# 20190501.net
KiCad netlist of a schematic drawn in EAGLE
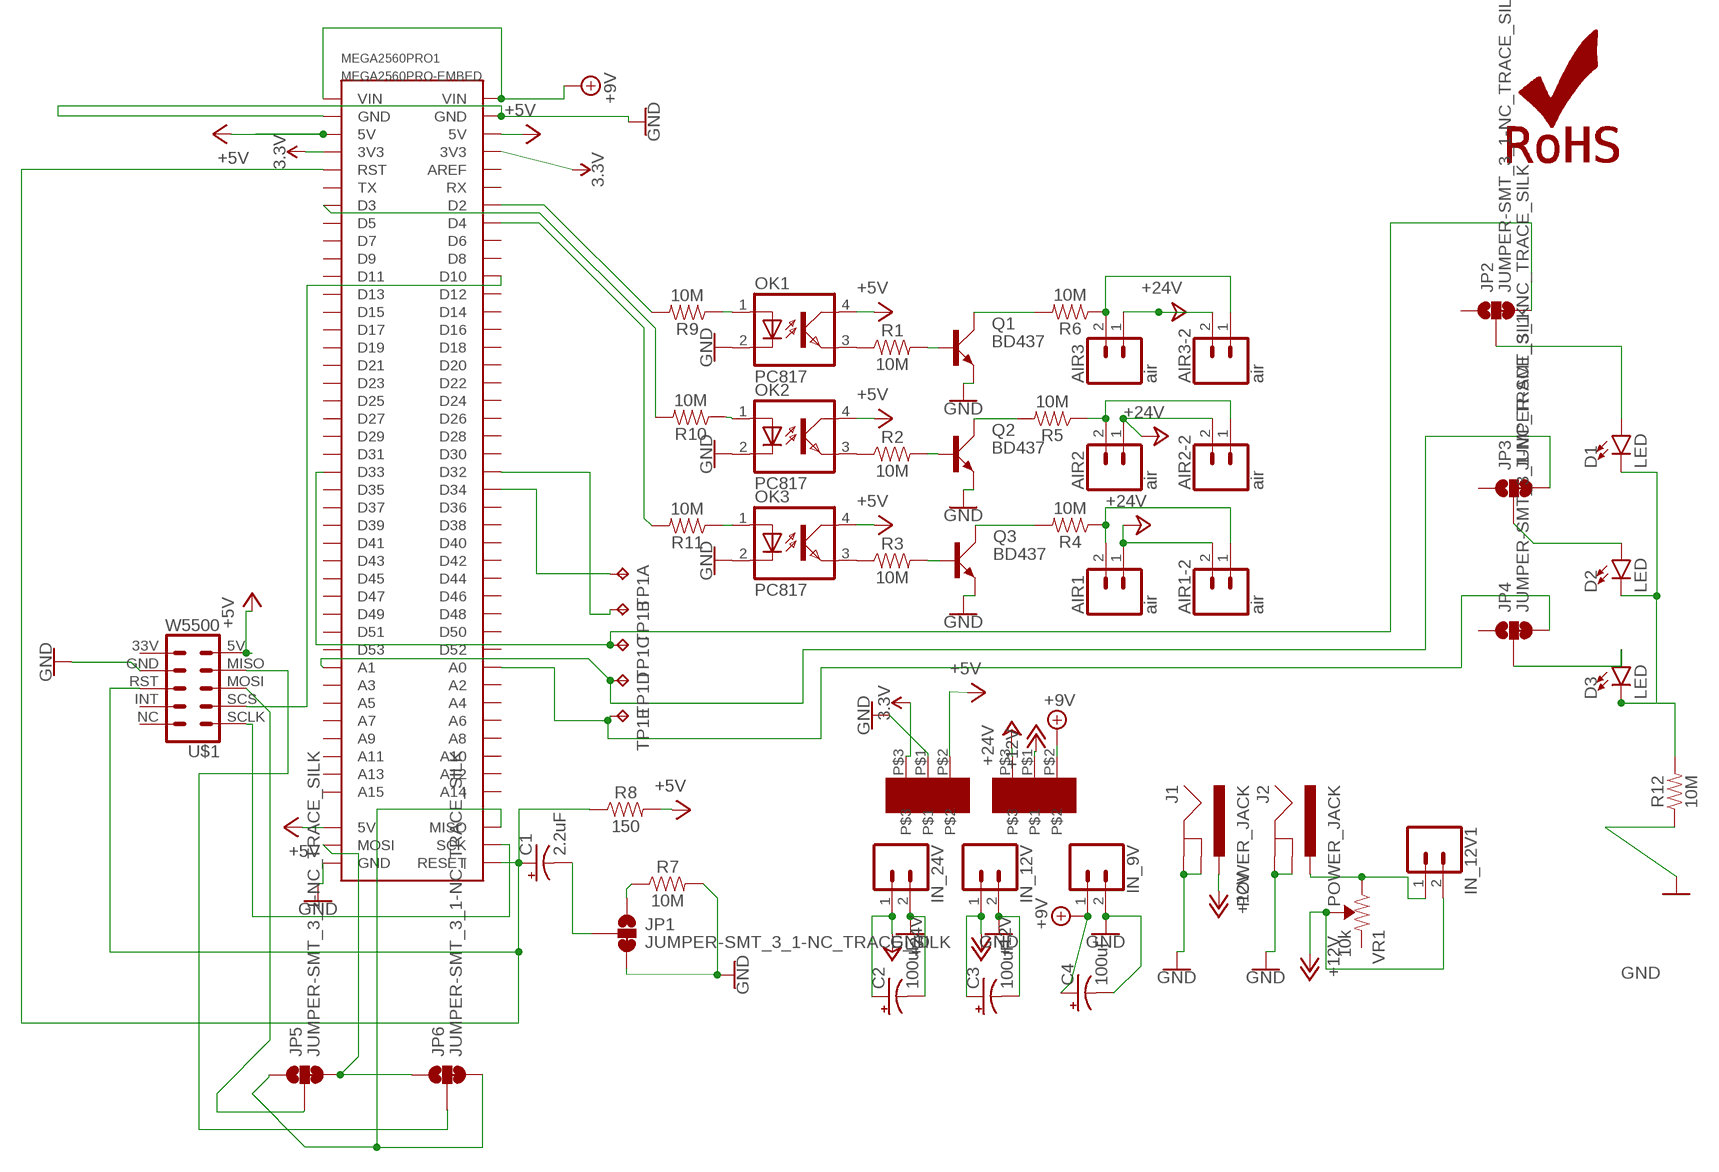
[diagram p0: schematic, sheet 1]

(export (version "E")
  (design (tool "Eeschema 10.0.6"))
  (components
    (comp (ref "AIR1")
      (value "air")
      (footprint "eagle-import:MOLEX-1X2_LOCK")
      (libsource (lib "eagle-import") (part "CONN_02POLAR_LOCK"))
    )
    (comp (ref "AIR1-2")
      (value "air")
      (footprint "eagle-import:1X02")
      (libsource (lib "eagle-import") (part "CONN_02"))
    )
    (comp (ref "AIR2")
      (value "air")
      (footprint "eagle-import:MOLEX-1X2_LOCK")
      (libsource (lib "eagle-import") (part "CONN_02POLAR_LOCK"))
    )
    (comp (ref "AIR2-2")
      (value "air")
      (footprint "eagle-import:1X02")
      (libsource (lib "eagle-import") (part "CONN_02"))
    )
    (comp (ref "AIR3")
      (value "air")
      (footprint "eagle-import:MOLEX-1X2_LOCK")
      (libsource (lib "eagle-import") (part "CONN_02POLAR_LOCK"))
    )
    (comp (ref "AIR3-2")
      (value "air")
      (footprint "eagle-import:1X02")
      (libsource (lib "eagle-import") (part "CONN_02"))
    )
    (comp (ref "C1")
      (value "2.2uF")
      (footprint "eagle-import:CPOL-RADIAL-2.5MM-5MM-KIT")
      (libsource (lib "eagle-import") (part "10UF-POLAR-RADIAL-2.5MM-KIT-25V-20%"))
    )
    (comp (ref "C2")
      (value "100uF")
      (footprint "eagle-import:CPOL-RADIAL-2.5MM-6.5MM")
      (libsource (lib "eagle-import") (part "100UF-POLAR-RADIAL-2.5MM-25V-20%"))
    )
    (comp (ref "C3")
      (value "100uF")
      (footprint "eagle-import:CPOL-RADIAL-2.5MM-6.5MM")
      (libsource (lib "eagle-import") (part "100UF-POLAR-RADIAL-2.5MM-25V-20%"))
    )
    (comp (ref "C4")
      (value "100uF")
      (footprint "eagle-import:CPOL-RADIAL-2.5MM-6.5MM")
      (libsource (lib "eagle-import") (part "100UF-POLAR-RADIAL-2.5MM-25V-20%"))
    )
    (comp (ref "D1")
      (value "LED")
      (footprint "eagle-import:LED_5MM")
      (libsource (lib "eagle-import") (part "LED5MM"))
    )
    (comp (ref "D2")
      (value "LED")
      (footprint "eagle-import:LED_5MM")
      (libsource (lib "eagle-import") (part "LED5MM"))
    )
    (comp (ref "D3")
      (value "LED")
      (footprint "eagle-import:LED_5MM")
      (libsource (lib "eagle-import") (part "LED5MM"))
    )
    (comp (ref "IN_9V")
      (value "CONN_02POLAR_LOCK")
      (footprint "eagle-import:MOLEX-1X2_LOCK")
      (libsource (lib "eagle-import") (part "CONN_02POLAR_LOCK"))
    )
    (comp (ref "IN_12V")
      (value "CONN_02POLAR_LOCK")
      (footprint "eagle-import:MOLEX-1X2_LOCK")
      (libsource (lib "eagle-import") (part "CONN_02POLAR_LOCK"))
    )
    (comp (ref "IN_12V1")
      (value "CONN_02POLAR_LOCK")
      (footprint "eagle-import:MOLEX-1X2_LOCK")
      (libsource (lib "eagle-import") (part "CONN_02POLAR_LOCK"))
    )
    (comp (ref "IN_24V")
      (value "CONN_02POLAR_LOCK")
      (footprint "eagle-import:MOLEX-1X2_LOCK")
      (libsource (lib "eagle-import") (part "CONN_02POLAR_LOCK"))
    )
    (comp (ref "J1")
      (value "POWER_JACK")
      (footprint "eagle-import:POWER_JACK_PTH")
      (libsource (lib "eagle-import") (part "POWER_JACK"))
    )
    (comp (ref "J2")
      (value "POWER_JACK")
      (footprint "eagle-import:POWER_JACK_PTH")
      (libsource (lib "eagle-import") (part "POWER_JACK"))
    )
    (comp (ref "JP1")
      (value "JUMPER-SMT_3_1-NC_TRACE_SILK")
      (footprint "eagle-import:SMT-JUMPER_3_1-NC_TRACE_SILK")
      (libsource (lib "eagle-import") (part "JUMPER-SMT_3_1-NC_TRACE_SILK"))
    )
    (comp (ref "JP2")
      (value "JUMPER-SMT_3_1-NC_TRACE_SILK")
      (footprint "eagle-import:SMT-JUMPER_3_1-NC_TRACE_SILK")
      (libsource (lib "eagle-import") (part "JUMPER-SMT_3_1-NC_TRACE_SILK"))
    )
    (comp (ref "JP3")
      (value "JUMPER-SMT_3_1-NC_TRACE_SILK")
      (footprint "eagle-import:SMT-JUMPER_3_1-NC_TRACE_SILK")
      (libsource (lib "eagle-import") (part "JUMPER-SMT_3_1-NC_TRACE_SILK"))
    )
    (comp (ref "JP4")
      (value "JUMPER-SMT_3_1-NC_TRACE_SILK")
      (footprint "eagle-import:SMT-JUMPER_3_1-NC_TRACE_SILK")
      (libsource (lib "eagle-import") (part "JUMPER-SMT_3_1-NC_TRACE_SILK"))
    )
    (comp (ref "JP5")
      (value "JUMPER-SMT_3_1-NC_TRACE_SILK")
      (footprint "eagle-import:SMT-JUMPER_3_1-NC_TRACE_SILK")
      (libsource (lib "eagle-import") (part "JUMPER-SMT_3_1-NC_TRACE_SILK"))
    )
    (comp (ref "JP6")
      (value "JUMPER-SMT_3_1-NC_TRACE_SILK")
      (footprint "eagle-import:SMT-JUMPER_3_1-NC_TRACE_SILK")
      (libsource (lib "eagle-import") (part "JUMPER-SMT_3_1-NC_TRACE_SILK"))
    )
    (comp (ref "LOGO1")
      (value "ROHS_LOGO")
      (footprint "eagle-import:ROHS_LOGO_0.18_IN")
      (libsource (lib "eagle-import") (part "ROHS_LOGO"))
    )
    (comp (ref "MEGA2560PRO1")
      (value "MEGA2560PRO-EMBED")
      (footprint "eagle-import:MEGA2560PRO-EMBED")
      (libsource (lib "eagle-import") (part "MEGA2560PRO-EMBED"))
    )
    (comp (ref "OK1")
      (value "PC817")
      (footprint "eagle-import:DIL04")
      (fields (field (name "MPN") "PC817X4J000F"))
      (libsource (lib "eagle-import") (part "PC817"))
    )
    (comp (ref "OK2")
      (value "PC817")
      (footprint "eagle-import:DIL04")
      (fields (field (name "MPN") "PC817X4J000F"))
      (libsource (lib "eagle-import") (part "PC817"))
    )
    (comp (ref "OK3")
      (value "PC817")
      (footprint "eagle-import:DIL04")
      (fields (field (name "MPN") "PC817X4J000F"))
      (libsource (lib "eagle-import") (part "PC817"))
    )
    (comp (ref "Q1")
      (value "BD437")
      (footprint "eagle-import:TO126AV")
      (libsource (lib "eagle-import") (part "BD437"))
    )
    (comp (ref "Q2")
      (value "BD437")
      (footprint "eagle-import:TO126AV")
      (libsource (lib "eagle-import") (part "BD437"))
    )
    (comp (ref "Q3")
      (value "BD437")
      (footprint "eagle-import:TO126AV")
      (libsource (lib "eagle-import") (part "BD437"))
    )
    (comp (ref "R1")
      (value "10M")
      (footprint "eagle-import:AXIAL-0.3")
      (libsource (lib "eagle-import") (part "10MOHM-HORIZ-1/4W-5%"))
    )
    (comp (ref "R2")
      (value "10M")
      (footprint "eagle-import:AXIAL-0.3")
      (libsource (lib "eagle-import") (part "10MOHM-HORIZ-1/4W-5%"))
    )
    (comp (ref "R3")
      (value "10M")
      (footprint "eagle-import:AXIAL-0.3")
      (libsource (lib "eagle-import") (part "10MOHM-HORIZ-1/4W-5%"))
    )
    (comp (ref "R4")
      (value "10M")
      (footprint "eagle-import:AXIAL-0.3")
      (libsource (lib "eagle-import") (part "10MOHM-HORIZ-1/4W-5%"))
    )
    (comp (ref "R5")
      (value "10M")
      (footprint "eagle-import:AXIAL-0.3")
      (libsource (lib "eagle-import") (part "10MOHM-HORIZ-1/4W-5%"))
    )
    (comp (ref "R6")
      (value "10M")
      (footprint "eagle-import:AXIAL-0.3")
      (libsource (lib "eagle-import") (part "10MOHM-HORIZ-1/4W-5%"))
    )
    (comp (ref "R7")
      (value "10M")
      (footprint "eagle-import:AXIAL-0.3")
      (libsource (lib "eagle-import") (part "10MOHM-HORIZ-1/4W-5%"))
    )
    (comp (ref "R8")
      (value "150")
      (footprint "eagle-import:AXIAL-0.3")
      (libsource (lib "eagle-import") (part "10MOHM-HORIZ-1/4W-5%"))
    )
    (comp (ref "R9")
      (value "10M")
      (footprint "eagle-import:AXIAL-0.3")
      (libsource (lib "eagle-import") (part "10MOHM-HORIZ-1/4W-5%"))
    )
    (comp (ref "R10")
      (value "10M")
      (footprint "eagle-import:AXIAL-0.3")
      (libsource (lib "eagle-import") (part "10MOHM-HORIZ-1/4W-5%"))
    )
    (comp (ref "R11")
      (value "10M")
      (footprint "eagle-import:AXIAL-0.3")
      (libsource (lib "eagle-import") (part "10MOHM-HORIZ-1/4W-5%"))
    )
    (comp (ref "R12")
      (value "10M")
      (footprint "eagle-import:AXIAL-0.3")
      (libsource (lib "eagle-import") (part "10MOHM-HORIZ-1/4W-5%"))
    )
    (comp (ref "TP1")
      (value "TP5P5-25-13")
      (footprint "eagle-import:P5-25-13")
      (libsource (lib "eagle-import") (part "TP5P5-25-13"))
    )
    (comp (ref "U$1")
      (value "W5500")
      (footprint "eagle-import:W5500")
      (libsource (lib "eagle-import") (part "W5500"))
    )
    (comp (ref "U$2")
      (value "AC_3PINAC3PIN7MM")
      (footprint "eagle-import:AC3PIN7MM")
      (libsource (lib "eagle-import") (part "AC_3PINAC3PIN7MM"))
    )
    (comp (ref "U$4")
      (value "AC_3PINAC3PIN7MM")
      (footprint "eagle-import:AC3PIN7MM")
      (libsource (lib "eagle-import") (part "AC_3PINAC3PIN7MM"))
    )
    (comp (ref "VR1")
      (value "10k")
      (footprint "eagle-import:TRIMPOT-PTH-3386U")
      (libsource (lib "eagle-import") (part "TRIMPOT-PTH-10MM-KNOB-1/2W-10%"))
    )
  )
  (nets
    (net (code "1") (name "+5V") (class "Default")
      (node (ref "MEGA2560PRO1") (pin "5V@1") (pinfunction "5V_5V@1") (pintype "bidirectional"))
      (node (ref "MEGA2560PRO1") (pin "5V@2") (pinfunction "5V_5V@2") (pintype "bidirectional"))
      (node (ref "MEGA2560PRO1") (pin "5V@3") (pinfunction "5V_5V@3") (pintype "bidirectional"))
      (node (ref "OK1") (pin "4") (pinfunction "COL_4") (pintype "passive"))
      (node (ref "OK2") (pin "4") (pinfunction "COL_4") (pintype "passive"))
      (node (ref "OK3") (pin "4") (pinfunction "COL_4") (pintype "passive"))
      (node (ref "R8") (pin "P$2") (pinfunction "2_P$2") (pintype "passive"))
      (node (ref "U$1") (pin "5V") (pinfunction "9_5V") (pintype "passive"))
      (node (ref "U$4") (pin "P$2") (pinfunction "P$2_P$2") (pintype "bidirectional"))
    )
    (net (code "2") (name "+9V") (class "Default")
      (node (ref "C4") (pin "1") (pinfunction "+_1") (pintype "passive"))
      (node (ref "IN_9V") (pin "1") (pinfunction "1_1") (pintype "passive"))
      (node (ref "MEGA2560PRO1") (pin "VIN@1") (pinfunction "VIN_VIN@1") (pintype "bidirectional"))
      (node (ref "MEGA2560PRO1") (pin "VIN@2") (pinfunction "VIN_VIN@2") (pintype "bidirectional"))
      (node (ref "U$2") (pin "P$2") (pinfunction "P$2_P$2") (pintype "bidirectional"))
    )
    (net (code "3") (name "+12V") (class "Default")
      (node (ref "C3") (pin "1") (pinfunction "+_1") (pintype "passive"))
      (node (ref "IN_12V") (pin "1") (pinfunction "1_1") (pintype "passive"))
      (node (ref "IN_12V1") (pin "2") (pinfunction "2_2") (pintype "passive"))
      (node (ref "J1") (pin "PWR") (pinfunction "PWR_PWR") (pintype "bidirectional"))
      (node (ref "U$2") (pin "P$1") (pinfunction "P$1_P$1") (pintype "bidirectional"))
      (node (ref "VR1") (pin "2") (pinfunction "WIPER_2") (pintype "passive"))
    )
    (net (code "4") (name "+24V") (class "Default")
      (node (ref "AIR1") (pin "1") (pinfunction "1_1") (pintype "passive"))
      (node (ref "AIR1-2") (pin "2") (pinfunction "2_2") (pintype "passive"))
      (node (ref "AIR2") (pin "1") (pinfunction "1_1") (pintype "passive"))
      (node (ref "AIR2-2") (pin "2") (pinfunction "2_2") (pintype "passive"))
      (node (ref "AIR3") (pin "1") (pinfunction "1_1") (pintype "passive"))
      (node (ref "AIR3-2") (pin "2") (pinfunction "2_2") (pintype "passive"))
      (node (ref "C2") (pin "1") (pinfunction "+_1") (pintype "passive"))
      (node (ref "IN_24V") (pin "1") (pinfunction "1_1") (pintype "passive"))
      (node (ref "U$2") (pin "P$3") (pinfunction "P$3_P$3") (pintype "bidirectional"))
    )
    (net (code "5") (name "3.3V") (class "Default")
      (node (ref "MEGA2560PRO1") (pin "3V3@1") (pinfunction "3V3_3V3@1") (pintype "bidirectional"))
      (node (ref "MEGA2560PRO1") (pin "3V3@2") (pinfunction "3V3_3V3@2") (pintype "bidirectional"))
      (node (ref "U$4") (pin "P$3") (pinfunction "P$3_P$3") (pintype "bidirectional"))
    )
    (net (code "6") (name "GND") (class "Default")
      (node (ref "C2") (pin "2") (pinfunction "-_2") (pintype "passive"))
      (node (ref "C3") (pin "2") (pinfunction "-_2") (pintype "passive"))
      (node (ref "C4") (pin "2") (pinfunction "-_2") (pintype "passive"))
      (node (ref "IN_12V") (pin "2") (pinfunction "2_2") (pintype "passive"))
      (node (ref "IN_24V") (pin "2") (pinfunction "2_2") (pintype "passive"))
      (node (ref "IN_9V") (pin "2") (pinfunction "2_2") (pintype "passive"))
      (node (ref "J1") (pin "GND") (pinfunction "GND_GND") (pintype "bidirectional"))
      (node (ref "J1") (pin "GNDBREAK") (pinfunction "GNDBREAK_GNDBREAK") (pintype "bidirectional"))
      (node (ref "J2") (pin "GND") (pinfunction "GND_GND") (pintype "bidirectional"))
      (node (ref "J2") (pin "GNDBREAK") (pinfunction "GNDBREAK_GNDBREAK") (pintype "bidirectional"))
      (node (ref "JP1") (pin "3") (pinfunction "3_3") (pintype "passive"))
      (node (ref "MEGA2560PRO1") (pin "GND@1") (pinfunction "GND_GND@1") (pintype "bidirectional"))
      (node (ref "MEGA2560PRO1") (pin "GND@2") (pinfunction "GND_GND@2") (pintype "bidirectional"))
      (node (ref "MEGA2560PRO1") (pin "GND@3") (pinfunction "GND_GND@3") (pintype "bidirectional"))
      (node (ref "OK1") (pin "2") (pinfunction "C_2") (pintype "passive"))
      (node (ref "OK2") (pin "2") (pinfunction "C_2") (pintype "passive"))
      (node (ref "OK3") (pin "2") (pinfunction "C_2") (pintype "passive"))
      (node (ref "Q1") (pin "E") (pinfunction "E_E") (pintype "passive"))
      (node (ref "Q2") (pin "E") (pinfunction "E_E") (pintype "passive"))
      (node (ref "Q3") (pin "E") (pinfunction "E_E") (pintype "passive"))
      (node (ref "R12") (pin "P$1") (pinfunction "1_P$1") (pintype "passive"))
      (node (ref "R7") (pin "P$2") (pinfunction "2_P$2") (pintype "passive"))
      (node (ref "U$1") (pin "GND") (pinfunction "8_GND") (pintype "passive"))
      (node (ref "U$4") (pin "P$1") (pinfunction "P$1_P$1") (pintype "bidirectional"))
    )
    (net (code "7") (name "Net-(C1-+)") (class "Default")
      (node (ref "C1") (pin "1") (pinfunction "+_1") (pintype "passive"))
      (node (ref "MEGA2560PRO1") (pin "RESET") (pinfunction "RESET_RESET") (pintype "bidirectional"))
      (node (ref "MEGA2560PRO1") (pin "RST") (pinfunction "RST_RST") (pintype "bidirectional"))
      (node (ref "R8") (pin "P$1") (pinfunction "1_P$1") (pintype "passive"))
      (node (ref "U$1") (pin "RST") (pinfunction "6_RST") (pintype "passive"))
    )
    (net (code "8") (name "Net-(C1--)") (class "Default")
      (node (ref "C1") (pin "2") (pinfunction "-_2") (pintype "passive"))
      (node (ref "JP1") (pin "2") (pinfunction "2_2") (pintype "passive"))
    )
    (net (code "9") (name "Net-(D1-C)") (class "Default")
      (node (ref "D1") (pin "K") (pinfunction "C_K") (pintype "passive"))
      (node (ref "D2") (pin "K") (pinfunction "C_K") (pintype "passive"))
      (node (ref "D3") (pin "K") (pinfunction "C_K") (pintype "passive"))
      (node (ref "R12") (pin "P$2") (pinfunction "2_P$2") (pintype "passive"))
    )
    (net (code "10") (name "Net-(D1-PadA)") (class "Default")
      (node (ref "D1") (pin "A") (pinfunction "A_A") (pintype "passive"))
      (node (ref "JP2") (pin "2") (pinfunction "2_2") (pintype "passive"))
    )
    (net (code "11") (name "Net-(D2-PadA)") (class "Default")
      (node (ref "D2") (pin "A") (pinfunction "A_A") (pintype "passive"))
      (node (ref "JP3") (pin "2") (pinfunction "2_2") (pintype "passive"))
    )
    (net (code "12") (name "Net-(D3-PadA)") (class "Default")
      (node (ref "D3") (pin "A") (pinfunction "A_A") (pintype "passive"))
      (node (ref "JP4") (pin "2") (pinfunction "2_2") (pintype "passive"))
    )
    (net (code "13") (name "Net-(JP5-Pad1)") (class "Default")
      (node (ref "JP5") (pin "1") (pinfunction "1_1") (pintype "passive"))
      (node (ref "JP6") (pin "3") (pinfunction "3_3") (pintype "passive"))
      (node (ref "MEGA2560PRO1") (pin "MISO") (pinfunction "MISO_MISO") (pintype "bidirectional"))
    )
    (net (code "14") (name "Net-(JP5-Pad3)") (class "Default")
      (node (ref "JP5") (pin "3") (pinfunction "3_3") (pintype "passive"))
      (node (ref "JP6") (pin "1") (pinfunction "1_1") (pintype "passive"))
      (node (ref "MEGA2560PRO1") (pin "MOSI") (pinfunction "MOSI_MOSI") (pintype "bidirectional"))
    )
    (net (code "15") (name "Net-(OK1-A)") (class "Default")
      (node (ref "OK1") (pin "1") (pinfunction "A_1") (pintype "passive"))
      (node (ref "R9") (pin "P$1") (pinfunction "1_P$1") (pintype "passive"))
    )
    (net (code "16") (name "Net-(OK1-EMIT)") (class "Default")
      (node (ref "OK1") (pin "3") (pinfunction "EMIT_3") (pintype "passive"))
      (node (ref "R1") (pin "P$1") (pinfunction "1_P$1") (pintype "passive"))
    )
    (net (code "17") (name "Net-(OK2-A)") (class "Default")
      (node (ref "OK2") (pin "1") (pinfunction "A_1") (pintype "passive"))
      (node (ref "R10") (pin "P$1") (pinfunction "1_P$1") (pintype "passive"))
    )
    (net (code "18") (name "Net-(OK2-EMIT)") (class "Default")
      (node (ref "OK2") (pin "3") (pinfunction "EMIT_3") (pintype "passive"))
      (node (ref "R2") (pin "P$1") (pinfunction "1_P$1") (pintype "passive"))
    )
    (net (code "19") (name "Net-(OK3-A)") (class "Default")
      (node (ref "OK3") (pin "1") (pinfunction "A_1") (pintype "passive"))
      (node (ref "R11") (pin "P$1") (pinfunction "1_P$1") (pintype "passive"))
    )
    (net (code "20") (name "Net-(OK3-EMIT)") (class "Default")
      (node (ref "OK3") (pin "3") (pinfunction "EMIT_3") (pintype "passive"))
      (node (ref "R3") (pin "P$1") (pinfunction "1_P$1") (pintype "passive"))
    )
    (net (code "21") (name "Net-(R1-2)") (class "Default")
      (node (ref "Q1") (pin "B") (pinfunction "B_B") (pintype "passive"))
      (node (ref "R1") (pin "P$2") (pinfunction "2_P$2") (pintype "passive"))
    )
    (net (code "22") (name "Net-(R2-2)") (class "Default")
      (node (ref "Q2") (pin "B") (pinfunction "B_B") (pintype "passive"))
      (node (ref "R2") (pin "P$2") (pinfunction "2_P$2") (pintype "passive"))
    )
    (net (code "23") (name "Net-(R3-2)") (class "Default")
      (node (ref "Q3") (pin "B") (pinfunction "B_B") (pintype "passive"))
      (node (ref "R3") (pin "P$2") (pinfunction "2_P$2") (pintype "passive"))
    )
    (net (code "24") (name "Net-(R4-1)") (class "Default")
      (node (ref "AIR1") (pin "2") (pinfunction "2_2") (pintype "passive"))
      (node (ref "AIR1-2") (pin "1") (pinfunction "1_1") (pintype "passive"))
      (node (ref "R4") (pin "P$1") (pinfunction "1_P$1") (pintype "passive"))
    )
    (net (code "25") (name "Net-(R4-2)") (class "Default")
      (node (ref "Q3") (pin "C") (pinfunction "C_C") (pintype "passive"))
      (node (ref "R4") (pin "P$2") (pinfunction "2_P$2") (pintype "passive"))
    )
    (net (code "26") (name "Net-(R5-1)") (class "Default")
      (node (ref "AIR2") (pin "2") (pinfunction "2_2") (pintype "passive"))
      (node (ref "AIR2-2") (pin "1") (pinfunction "1_1") (pintype "passive"))
      (node (ref "R5") (pin "P$1") (pinfunction "1_P$1") (pintype "passive"))
    )
    (net (code "27") (name "Net-(R5-2)") (class "Default")
      (node (ref "Q2") (pin "C") (pinfunction "C_C") (pintype "passive"))
      (node (ref "R5") (pin "P$2") (pinfunction "2_P$2") (pintype "passive"))
    )
    (net (code "28") (name "Net-(R6-1)") (class "Default")
      (node (ref "AIR3") (pin "2") (pinfunction "2_2") (pintype "passive"))
      (node (ref "AIR3-2") (pin "1") (pinfunction "1_1") (pintype "passive"))
      (node (ref "R6") (pin "P$1") (pinfunction "1_P$1") (pintype "passive"))
    )
    (net (code "29") (name "Net-(R6-2)") (class "Default")
      (node (ref "Q1") (pin "C") (pinfunction "C_C") (pintype "passive"))
      (node (ref "R6") (pin "P$2") (pinfunction "2_P$2") (pintype "passive"))
    )
    (net (code "30") (name "Net-(R7-1)") (class "Default")
      (node (ref "JP1") (pin "1") (pinfunction "1_1") (pintype "passive"))
      (node (ref "R7") (pin "P$1") (pinfunction "1_P$1") (pintype "passive"))
    )
    (net (code "31") (name "Net-(R9-2)") (class "Default")
      (node (ref "MEGA2560PRO1") (pin "D2") (pinfunction "D2_D2") (pintype "bidirectional"))
      (node (ref "R9") (pin "P$2") (pinfunction "2_P$2") (pintype "passive"))
    )
    (net (code "32") (name "Net-(R10-2)") (class "Default")
      (node (ref "MEGA2560PRO1") (pin "D3") (pinfunction "D3_D3") (pintype "bidirectional"))
      (node (ref "R10") (pin "P$2") (pinfunction "2_P$2") (pintype "passive"))
    )
    (net (code "33") (name "Net-(R11-2)") (class "Default")
      (node (ref "MEGA2560PRO1") (pin "D4") (pinfunction "D4_D4") (pintype "bidirectional"))
      (node (ref "R11") (pin "P$2") (pinfunction "2_P$2") (pintype "passive"))
    )
    (net (code "34") (name "Net-(TP1A-TP)") (class "Default")
      (node (ref "MEGA2560PRO1") (pin "D34") (pinfunction "D34_D34") (pintype "bidirectional"))
      (node (ref "TP1") (pin "TP-1") (pinfunction "TP_TP-1") (pintype "input"))
    )
    (net (code "35") (name "Net-(TP1B-TP)") (class "Default")
      (node (ref "MEGA2560PRO1") (pin "D32") (pinfunction "D32_D32") (pintype "bidirectional"))
      (node (ref "TP1") (pin "TP-2") (pinfunction "TP_TP-2") (pintype "input"))
    )
    (net (code "36") (name "Net-(TP1C-TP)") (class "Default")
      (node (ref "JP2") (pin "3") (pinfunction "3_3") (pintype "passive"))
      (node (ref "MEGA2560PRO1") (pin "D33") (pinfunction "D33_D33") (pintype "bidirectional"))
      (node (ref "TP1") (pin "TP-3") (pinfunction "TP_TP-3") (pintype "input"))
    )
    (net (code "37") (name "Net-(TP1D-TP)") (class "Default")
      (node (ref "JP3") (pin "3") (pinfunction "3_3") (pintype "passive"))
      (node (ref "MEGA2560PRO1") (pin "A1") (pinfunction "A1_A1") (pintype "bidirectional"))
      (node (ref "TP1") (pin "TP-4") (pinfunction "TP_TP-4") (pintype "input"))
    )
    (net (code "38") (name "Net-(TP1E-TP)") (class "Default")
      (node (ref "JP4") (pin "3") (pinfunction "3_3") (pintype "passive"))
      (node (ref "MEGA2560PRO1") (pin "A0") (pinfunction "A0_A0") (pintype "bidirectional"))
      (node (ref "TP1") (pin "TP-5") (pinfunction "TP_TP-5") (pintype "input"))
    )
    (net (code "39") (name "Net-(U$1-3)") (class "Default")
      (node (ref "MEGA2560PRO1") (pin "D10") (pinfunction "D10_D10") (pintype "bidirectional"))
      (node (ref "U$1") (pin "SCS") (pinfunction "3_SCS") (pintype "passive"))
    )
    (net (code "40") (name "Net-(U$1-5)") (class "Default")
      (node (ref "JP5") (pin "2") (pinfunction "2_2") (pintype "passive"))
      (node (ref "U$1") (pin "MOSI") (pinfunction "5_MOSI") (pintype "passive"))
    )
    (net (code "41") (name "Net-(U$1-7)") (class "Default")
      (node (ref "JP6") (pin "2") (pinfunction "2_2") (pintype "passive"))
      (node (ref "U$1") (pin "MISO") (pinfunction "7_MISO") (pintype "passive"))
    )
    (net (code "42") (name "Net-(U$1-33V)") (class "Default")
      (node (ref "MEGA2560PRO1") (pin "SCK") (pinfunction "SCK_SCK") (pintype "bidirectional"))
      (node (ref "U$1") (pin "SCLK") (pinfunction "33V_SCLK") (pintype "passive"))
    )
    (net (code "43") (name "Net-(VR1-CW)") (class "Default")
      (node (ref "IN_12V1") (pin "1") (pinfunction "1_1") (pintype "passive"))
      (node (ref "J2") (pin "PWR") (pinfunction "PWR_PWR") (pintype "bidirectional"))
      (node (ref "VR1") (pin "3") (pinfunction "CW_3") (pintype "passive"))
    )
    (net (code "44") (name "unconnected-(JP2-Pad1)") (class "Default")
      (node (ref "JP2") (pin "1") (pinfunction "1_1") (pintype "passive"))
    )
    (net (code "45") (name "unconnected-(JP3-Pad1)") (class "Default")
      (node (ref "JP3") (pin "1") (pinfunction "1_1") (pintype "passive"))
    )
    (net (code "46") (name "unconnected-(JP4-Pad1)") (class "Default")
      (node (ref "JP4") (pin "1") (pinfunction "1_1") (pintype "passive"))
    )
    (net (code "47") (name "unconnected-(MEGA2560PRO1-PadA2)") (class "Default")
      (node (ref "MEGA2560PRO1") (pin "A2") (pinfunction "A2_A2") (pintype "bidirectional"))
    )
    (net (code "48") (name "unconnected-(MEGA2560PRO1-PadA3)") (class "Default")
      (node (ref "MEGA2560PRO1") (pin "A3") (pinfunction "A3_A3") (pintype "bidirectional"))
    )
    (net (code "49") (name "unconnected-(MEGA2560PRO1-PadA4)") (class "Default")
      (node (ref "MEGA2560PRO1") (pin "A4") (pinfunction "A4_A4") (pintype "bidirectional"))
    )
    (net (code "50") (name "unconnected-(MEGA2560PRO1-PadA5)") (class "Default")
      (node (ref "MEGA2560PRO1") (pin "A5") (pinfunction "A5_A5") (pintype "bidirectional"))
    )
    (net (code "51") (name "unconnected-(MEGA2560PRO1-PadA6)") (class "Default")
      (node (ref "MEGA2560PRO1") (pin "A6") (pinfunction "A6_A6") (pintype "bidirectional"))
    )
    (net (code "52") (name "unconnected-(MEGA2560PRO1-PadA7)") (class "Default")
      (node (ref "MEGA2560PRO1") (pin "A7") (pinfunction "A7_A7") (pintype "bidirectional"))
    )
    (net (code "53") (name "unconnected-(MEGA2560PRO1-PadA8)") (class "Default")
      (node (ref "MEGA2560PRO1") (pin "A8") (pinfunction "A8_A8") (pintype "bidirectional"))
    )
    (net (code "54") (name "unconnected-(MEGA2560PRO1-PadA9)") (class "Default")
      (node (ref "MEGA2560PRO1") (pin "A9") (pinfunction "A9_A9") (pintype "bidirectional"))
    )
    (net (code "55") (name "unconnected-(MEGA2560PRO1-PadA10)") (class "Default")
      (node (ref "MEGA2560PRO1") (pin "A10") (pinfunction "A10_A10") (pintype "bidirectional"))
    )
    (net (code "56") (name "unconnected-(MEGA2560PRO1-PadA11)") (class "Default")
      (node (ref "MEGA2560PRO1") (pin "A11") (pinfunction "A11_A11") (pintype "bidirectional"))
    )
    (net (code "57") (name "unconnected-(MEGA2560PRO1-PadA12)") (class "Default")
      (node (ref "MEGA2560PRO1") (pin "A12") (pinfunction "A12_A12") (pintype "bidirectional"))
    )
    (net (code "58") (name "unconnected-(MEGA2560PRO1-PadA13)") (class "Default")
      (node (ref "MEGA2560PRO1") (pin "A13") (pinfunction "A13_A13") (pintype "bidirectional"))
    )
    (net (code "59") (name "unconnected-(MEGA2560PRO1-PadA14)") (class "Default")
      (node (ref "MEGA2560PRO1") (pin "A14") (pinfunction "A14_A14") (pintype "bidirectional"))
    )
    (net (code "60") (name "unconnected-(MEGA2560PRO1-PadA15)") (class "Default")
      (node (ref "MEGA2560PRO1") (pin "A15") (pinfunction "A15_A15") (pintype "bidirectional"))
    )
    (net (code "61") (name "unconnected-(MEGA2560PRO1-PadAREF)") (class "Default")
      (node (ref "MEGA2560PRO1") (pin "AREF") (pinfunction "AREF_AREF") (pintype "bidirectional"))
    )
    (net (code "62") (name "unconnected-(MEGA2560PRO1-PadD5)") (class "Default")
      (node (ref "MEGA2560PRO1") (pin "D5") (pinfunction "D5_D5") (pintype "bidirectional"))
    )
    (net (code "63") (name "unconnected-(MEGA2560PRO1-PadD6)") (class "Default")
      (node (ref "MEGA2560PRO1") (pin "D6") (pinfunction "D6_D6") (pintype "bidirectional"))
    )
    (net (code "64") (name "unconnected-(MEGA2560PRO1-PadD7)") (class "Default")
      (node (ref "MEGA2560PRO1") (pin "D7") (pinfunction "D7_D7") (pintype "bidirectional"))
    )
    (net (code "65") (name "unconnected-(MEGA2560PRO1-PadD8)") (class "Default")
      (node (ref "MEGA2560PRO1") (pin "D8") (pinfunction "D8_D8") (pintype "bidirectional"))
    )
    (net (code "66") (name "unconnected-(MEGA2560PRO1-PadD9)") (class "Default")
      (node (ref "MEGA2560PRO1") (pin "D9") (pinfunction "D9_D9") (pintype "bidirectional"))
    )
    (net (code "67") (name "unconnected-(MEGA2560PRO1-PadD11)") (class "Default")
      (node (ref "MEGA2560PRO1") (pin "D11") (pinfunction "D11_D11") (pintype "bidirectional"))
    )
    (net (code "68") (name "unconnected-(MEGA2560PRO1-PadD12)") (class "Default")
      (node (ref "MEGA2560PRO1") (pin "D12") (pinfunction "D12_D12") (pintype "bidirectional"))
    )
    (net (code "69") (name "unconnected-(MEGA2560PRO1-PadD13)") (class "Default")
      (node (ref "MEGA2560PRO1") (pin "D13") (pinfunction "D13_D13") (pintype "bidirectional"))
    )
    (net (code "70") (name "unconnected-(MEGA2560PRO1-PadD14)") (class "Default")
      (node (ref "MEGA2560PRO1") (pin "D14") (pinfunction "D14_D14") (pintype "bidirectional"))
    )
    (net (code "71") (name "unconnected-(MEGA2560PRO1-PadD15)") (class "Default")
      (node (ref "MEGA2560PRO1") (pin "D15") (pinfunction "D15_D15") (pintype "bidirectional"))
    )
    (net (code "72") (name "unconnected-(MEGA2560PRO1-PadD16)") (class "Default")
      (node (ref "MEGA2560PRO1") (pin "D16") (pinfunction "D16_D16") (pintype "bidirectional"))
    )
    (net (code "73") (name "unconnected-(MEGA2560PRO1-PadD17)") (class "Default")
      (node (ref "MEGA2560PRO1") (pin "D17") (pinfunction "D17_D17") (pintype "bidirectional"))
    )
    (net (code "74") (name "unconnected-(MEGA2560PRO1-PadD18)") (class "Default")
      (node (ref "MEGA2560PRO1") (pin "D18") (pinfunction "D18_D18") (pintype "bidirectional"))
    )
    (net (code "75") (name "unconnected-(MEGA2560PRO1-PadD19)") (class "Default")
      (node (ref "MEGA2560PRO1") (pin "D19") (pinfunction "D19_D19") (pintype "bidirectional"))
    )
    (net (code "76") (name "unconnected-(MEGA2560PRO1-PadD20)") (class "Default")
      (node (ref "MEGA2560PRO1") (pin "D20") (pinfunction "D20_D20") (pintype "bidirectional"))
    )
    (net (code "77") (name "unconnected-(MEGA2560PRO1-PadD21)") (class "Default")
      (node (ref "MEGA2560PRO1") (pin "D21") (pinfunction "D21_D21") (pintype "bidirectional"))
    )
    (net (code "78") (name "unconnected-(MEGA2560PRO1-PadD22)") (class "Default")
      (node (ref "MEGA2560PRO1") (pin "D22") (pinfunction "D22_D22") (pintype "bidirectional"))
    )
    (net (code "79") (name "unconnected-(MEGA2560PRO1-PadD23)") (class "Default")
      (node (ref "MEGA2560PRO1") (pin "D23") (pinfunction "D23_D23") (pintype "bidirectional"))
    )
    (net (code "80") (name "unconnected-(MEGA2560PRO1-PadD24)") (class "Default")
      (node (ref "MEGA2560PRO1") (pin "D24") (pinfunction "D24_D24") (pintype "bidirectional"))
    )
    (net (code "81") (name "unconnected-(MEGA2560PRO1-PadD25)") (class "Default")
      (node (ref "MEGA2560PRO1") (pin "D25") (pinfunction "D25_D25") (pintype "bidirectional"))
    )
    (net (code "82") (name "unconnected-(MEGA2560PRO1-PadD26)") (class "Default")
      (node (ref "MEGA2560PRO1") (pin "D26") (pinfunction "D26_D26") (pintype "bidirectional"))
    )
    (net (code "83") (name "unconnected-(MEGA2560PRO1-PadD27)") (class "Default")
      (node (ref "MEGA2560PRO1") (pin "D27") (pinfunction "D27_D27") (pintype "bidirectional"))
    )
    (net (code "84") (name "unconnected-(MEGA2560PRO1-PadD28)") (class "Default")
      (node (ref "MEGA2560PRO1") (pin "D28") (pinfunction "D28_D28") (pintype "bidirectional"))
    )
    (net (code "85") (name "unconnected-(MEGA2560PRO1-PadD29)") (class "Default")
      (node (ref "MEGA2560PRO1") (pin "D29") (pinfunction "D29_D29") (pintype "bidirectional"))
    )
    (net (code "86") (name "unconnected-(MEGA2560PRO1-PadD30)") (class "Default")
      (node (ref "MEGA2560PRO1") (pin "D30") (pinfunction "D30_D30") (pintype "bidirectional"))
    )
    (net (code "87") (name "unconnected-(MEGA2560PRO1-PadD31)") (class "Default")
      (node (ref "MEGA2560PRO1") (pin "D31") (pinfunction "D31_D31") (pintype "bidirectional"))
    )
    (net (code "88") (name "unconnected-(MEGA2560PRO1-PadD35)") (class "Default")
      (node (ref "MEGA2560PRO1") (pin "D35") (pinfunction "D35_D35") (pintype "bidirectional"))
    )
    (net (code "89") (name "unconnected-(MEGA2560PRO1-PadD36)") (class "Default")
      (node (ref "MEGA2560PRO1") (pin "D36") (pinfunction "D36_D36") (pintype "bidirectional"))
    )
    (net (code "90") (name "unconnected-(MEGA2560PRO1-PadD37)") (class "Default")
      (node (ref "MEGA2560PRO1") (pin "D37") (pinfunction "D37_D37") (pintype "bidirectional"))
    )
    (net (code "91") (name "unconnected-(MEGA2560PRO1-PadD38)") (class "Default")
      (node (ref "MEGA2560PRO1") (pin "D38") (pinfunction "D38_D38") (pintype "bidirectional"))
    )
    (net (code "92") (name "unconnected-(MEGA2560PRO1-PadD39)") (class "Default")
      (node (ref "MEGA2560PRO1") (pin "D39") (pinfunction "D39_D39") (pintype "bidirectional"))
    )
    (net (code "93") (name "unconnected-(MEGA2560PRO1-PadD40)") (class "Default")
      (node (ref "MEGA2560PRO1") (pin "D40") (pinfunction "D40_D40") (pintype "bidirectional"))
    )
    (net (code "94") (name "unconnected-(MEGA2560PRO1-PadD41)") (class "Default")
      (node (ref "MEGA2560PRO1") (pin "D41") (pinfunction "D41_D41") (pintype "bidirectional"))
    )
    (net (code "95") (name "unconnected-(MEGA2560PRO1-PadD42)") (class "Default")
      (node (ref "MEGA2560PRO1") (pin "D42") (pinfunction "D42_D42") (pintype "bidirectional"))
    )
    (net (code "96") (name "unconnected-(MEGA2560PRO1-PadD43)") (class "Default")
      (node (ref "MEGA2560PRO1") (pin "D43") (pinfunction "D43_D43") (pintype "bidirectional"))
    )
    (net (code "97") (name "unconnected-(MEGA2560PRO1-PadD44)") (class "Default")
      (node (ref "MEGA2560PRO1") (pin "D44") (pinfunction "D44_D44") (pintype "bidirectional"))
    )
    (net (code "98") (name "unconnected-(MEGA2560PRO1-PadD45)") (class "Default")
      (node (ref "MEGA2560PRO1") (pin "D45") (pinfunction "D45_D45") (pintype "bidirectional"))
    )
    (net (code "99") (name "unconnected-(MEGA2560PRO1-PadD46)") (class "Default")
      (node (ref "MEGA2560PRO1") (pin "D46") (pinfunction "D46_D46") (pintype "bidirectional"))
    )
    (net (code "100") (name "unconnected-(MEGA2560PRO1-PadD47)") (class "Default")
      (node (ref "MEGA2560PRO1") (pin "D47") (pinfunction "D47_D47") (pintype "bidirectional"))
    )
    (net (code "101") (name "unconnected-(MEGA2560PRO1-PadD48)") (class "Default")
      (node (ref "MEGA2560PRO1") (pin "D48") (pinfunction "D48_D48") (pintype "bidirectional"))
    )
    (net (code "102") (name "unconnected-(MEGA2560PRO1-PadD49)") (class "Default")
      (node (ref "MEGA2560PRO1") (pin "D49") (pinfunction "D49_D49") (pintype "bidirectional"))
    )
    (net (code "103") (name "unconnected-(MEGA2560PRO1-PadD50)") (class "Default")
      (node (ref "MEGA2560PRO1") (pin "D50") (pinfunction "D50_D50") (pintype "bidirectional"))
    )
    (net (code "104") (name "unconnected-(MEGA2560PRO1-PadD51)") (class "Default")
      (node (ref "MEGA2560PRO1") (pin "D51") (pinfunction "D51_D51") (pintype "bidirectional"))
    )
    (net (code "105") (name "unconnected-(MEGA2560PRO1-PadD52)") (class "Default")
      (node (ref "MEGA2560PRO1") (pin "D52") (pinfunction "D52_D52") (pintype "bidirectional"))
    )
    (net (code "106") (name "unconnected-(MEGA2560PRO1-PadD53)") (class "Default")
      (node (ref "MEGA2560PRO1") (pin "D53") (pinfunction "D53_D53") (pintype "bidirectional"))
    )
    (net (code "107") (name "unconnected-(MEGA2560PRO1-PadRX)") (class "Default")
      (node (ref "MEGA2560PRO1") (pin "RX") (pinfunction "RX_RX") (pintype "bidirectional"))
    )
    (net (code "108") (name "unconnected-(MEGA2560PRO1-PadTX)") (class "Default")
      (node (ref "MEGA2560PRO1") (pin "TX") (pinfunction "TX_TX") (pintype "bidirectional"))
    )
    (net (code "109") (name "unconnected-(U$1-4-PadINT)") (class "Default")
      (node (ref "U$1") (pin "INT") (pinfunction "4_INT") (pintype "passive"))
    )
    (net (code "110") (name "unconnected-(U$1-5V-PadNC)") (class "Default")
      (node (ref "U$1") (pin "NC") (pinfunction "5V_NC") (pintype "passive"))
    )
    (net (code "111") (name "unconnected-(U$1-10-Pad33V)") (class "Default")
      (node (ref "U$1") (pin "33V") (pinfunction "10_33V") (pintype "passive"))
    )
    (net (code "112") (name "unconnected-(VR1-CCW-Pad1)") (class "Default")
      (node (ref "VR1") (pin "1") (pinfunction "CCW_1") (pintype "passive"))
    )
  )
)
